# STM32.net
KiCad netlist of a schematic drawn in Altium Designer
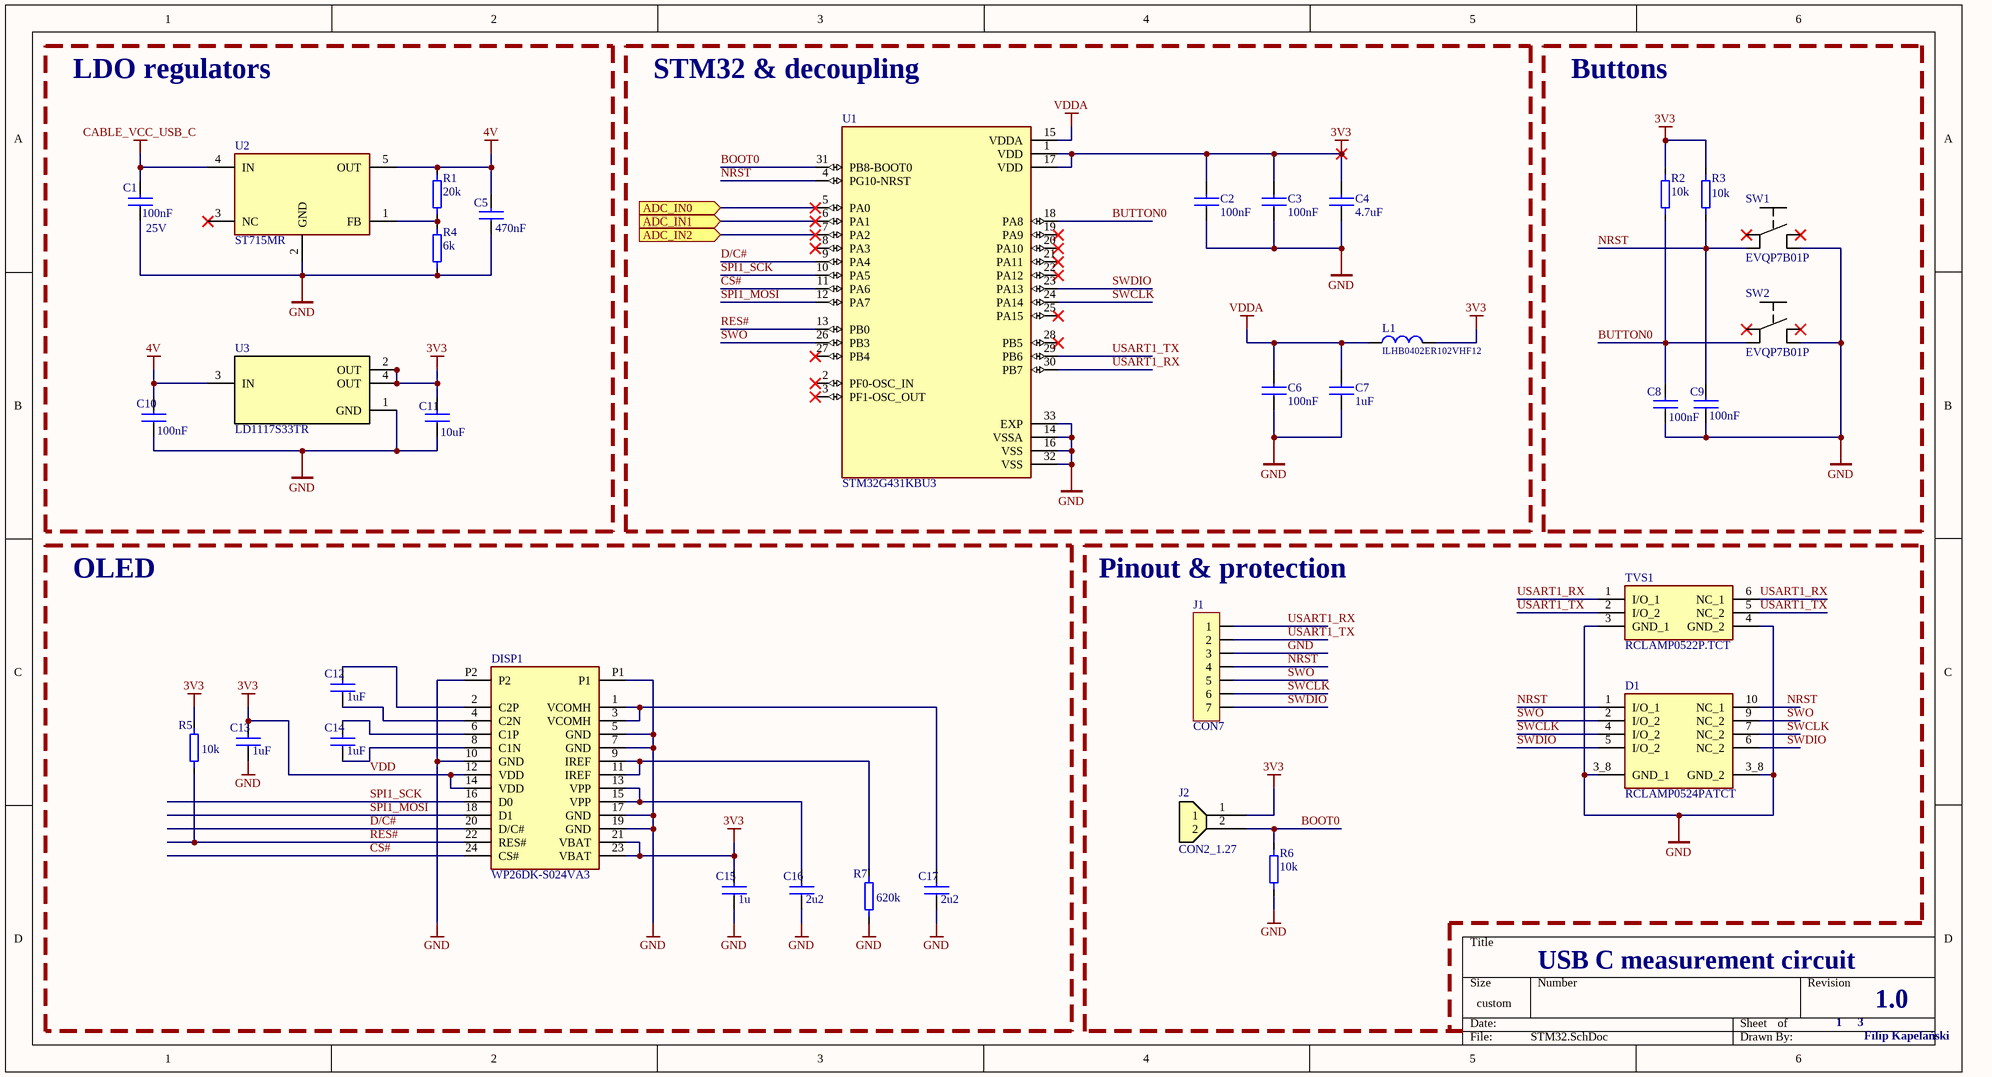
[diagram p0: STM32.SchDoc]

(export (version "E")
  (design (tool "Eeschema 10.0.6"))
  (components
    (comp (ref "C1")
      (value "100nF")
      (footprint "C0402")
      (description "Kondensator ceramiczny SMD")
      (fields (field (name "VOLTAGE") "25V"))
      (libsource (lib "n16_discrete") (part "C"))
    )
    (comp (ref "C2")
      (value "100nF")
      (footprint "C0402")
      (description "Kondensator ceramiczny SMD")
      (libsource (lib "n16_discrete") (part "C"))
    )
    (comp (ref "C3")
      (value "100nF")
      (footprint "C0402")
      (description "Kondensator ceramiczny SMD")
      (libsource (lib "n16_discrete") (part "C"))
    )
    (comp (ref "C4")
      (value "4.7uF")
      (footprint "C0402")
      (description "Kondensator ceramiczny SMD")
      (libsource (lib "n16_discrete") (part "C"))
    )
    (comp (ref "C5")
      (value "470nF")
      (footprint "C0402")
      (description "Kondensator ceramiczny SMD")
      (libsource (lib "n16_discrete") (part "C"))
    )
    (comp (ref "C6")
      (value "100nF")
      (footprint "C0402")
      (description "Kondensator ceramiczny SMD")
      (libsource (lib "n16_discrete") (part "C"))
    )
    (comp (ref "C7")
      (value "1uF")
      (footprint "C0402")
      (description "Kondensator ceramiczny SMD")
      (libsource (lib "n16_discrete") (part "C"))
    )
    (comp (ref "C8")
      (value "100nF")
      (footprint "C0402")
      (description "Kondensator ceramiczny SMD")
      (libsource (lib "n16_discrete") (part "C"))
    )
    (comp (ref "C9")
      (value "100nF")
      (footprint "C0402")
      (description "Kondensator ceramiczny SMD")
      (libsource (lib "n16_discrete") (part "C"))
    )
    (comp (ref "C10")
      (value "100nF")
      (footprint "C0402")
      (description "Kondensator ceramiczny SMD")
      (libsource (lib "n16_discrete") (part "C"))
    )
    (comp (ref "C11")
      (value "10uF")
      (footprint "C0402")
      (description "Kondensator ceramiczny SMD")
      (libsource (lib "n16_discrete") (part "C"))
    )
    (comp (ref "C12")
      (value "1uF")
      (footprint "C0402")
      (description "Kondensator ceramiczny SMD")
      (libsource (lib "n16_discrete") (part "C"))
    )
    (comp (ref "C13")
      (value "1uF")
      (footprint "C0402")
      (description "Kondensator ceramiczny SMD")
      (libsource (lib "n16_discrete") (part "C"))
    )
    (comp (ref "C14")
      (value "1uF")
      (footprint "C0402")
      (description "Kondensator ceramiczny SMD")
      (libsource (lib "n16_discrete") (part "C"))
    )
    (comp (ref "C15")
      (value "1u")
      (footprint "C0603")
      (description "Kondensator ceramiczny SMD")
      (libsource (lib "n16_discrete") (part "C"))
    )
    (comp (ref "C16")
      (value "2u2")
      (footprint "C0402")
      (description "Kondensator ceramiczny SMD")
      (libsource (lib "n16_discrete") (part "C"))
    )
    (comp (ref "C17")
      (value "2u2")
      (footprint "C0402")
      (description "Kondensator ceramiczny SMD")
      (libsource (lib "n16_discrete") (part "C"))
    )
    (comp (ref "D1")
      (value "RCLAMP0524PATCT")
      (footprint "DIO_RCLAMP0524PATCT")
      (description "15V Clamp 5A (8/20Âµs) Ipp Tvs Diode Surface Mount SLP2510P8")
      (fields (field (name "MF") "Semtech Corporation"))
      (libsource (lib "MyLibs") (part "RCLAMP0524PATCT"))
    )
    (comp (ref "DISP1")
      (value "WP26DK-S024VA3")
      (footprint "WP26DK-S024VA3")
      (libsource (lib "Optoelectronics") (part "WP26DK-S024VA3"))
    )
    (comp (ref "J1")
      (value "CON7")
      (footprint "SIP7")
      (description "Connector")
      (libsource (lib "n16_connector") (part "CON7"))
    )
    (comp (ref "J2")
      (value "CON2_1.27")
      (footprint "CON2_1.27")
      (description "Złącze: kołkowe; listwa kołkowa; męskie; PIN: 2; THT; proste; 1,27mm")
      (libsource (lib "n16_connector") (part "CON2_1.27"))
    )
    (comp (ref "L1")
      (value "ILHB0402ER102VHF12")
      (footprint "L0402")
      (description "Cewka/Koralik ferrytowy")
      (libsource (lib "n16_discrete") (part "L"))
    )
    (comp (ref "R1")
      (value "20k")
      (footprint "R0805")
      (description "Rezystor SMD")
      (libsource (lib "n16_discrete") (part "R"))
    )
    (comp (ref "R2")
      (value "10k")
      (footprint "R0402")
      (description "Rezystor SMD")
      (libsource (lib "n16_discrete") (part "R"))
    )
    (comp (ref "R3")
      (value "10k")
      (footprint "R0402")
      (description "Rezystor SMD")
      (libsource (lib "n16_discrete") (part "R"))
    )
    (comp (ref "R4")
      (value "6k")
      (footprint "R0805")
      (description "Rezystor SMD")
      (libsource (lib "n16_discrete") (part "R"))
    )
    (comp (ref "R5")
      (value "10k")
      (footprint "R0402")
      (description "Rezystor SMD")
      (libsource (lib "n16_discrete") (part "R"))
    )
    (comp (ref "R6")
      (value "10k")
      (footprint "R0402")
      (description "Rezystor SMD")
      (libsource (lib "uEproject23") (part "R"))
    )
    (comp (ref "R7")
      (value "620k")
      (footprint "R0402")
      (description "Rezystor SMD")
      (libsource (lib "n16_discrete") (part "R"))
    )
    (comp (ref "SW1")
      (value "EVQP7B01P")
      (footprint "EVQP7B01P")
      (description "Switch Tactile N.O. SPST Rectangular Button J-Bend 0.05A 12VDC 2.2N SMD T/R")
      (libsource (lib "Switche") (part "EVQP7B01P"))
    )
    (comp (ref "SW2")
      (value "EVQP7B01P")
      (footprint "EVQP7B01P")
      (description "Switch Tactile N.O. SPST Rectangular Button J-Bend 0.05A 12VDC 2.2N SMD T/R")
      (libsource (lib "Switche") (part "EVQP7B01P"))
    )
    (comp (ref "TVS1")
      (value "RCLAMP0522P.TCT")
      (footprint "RCLAMP0522PTCT")
      (description "TVS Diode (Bi-directional)")
      (fields (field (name "MOUSER PART NUMBER") "947-RCLAMP0522P.TCT"))
      (libsource (lib "MyLibs") (part "RCLAMP0522P.TCT"))
    )
    (comp (ref "U1")
      (value "STM32G431KBU3")
      (footprint "STM32G431KBU3")
      (libsource (lib "STM32") (part "STM32G431KBU3"))
    )
    (comp (ref "U2")
      (value "ST715MR")
      (footprint "ST715MR")
      (description "Linear Voltage Regulator IC Positive Adjustable 1 Output 85mA SOT-23-5")
      (libsource (lib "LDO") (part "ST715MR"))
    )
    (comp (ref "U3")
      (value "LD1117S33TR")
      (footprint "LD1117S33TR")
      (description "Linear Voltage Regulator IC Positive Fixed 1 Output 800mA SOT-223")
      (libsource (lib "LDO") (part "LD1117S33TR"))
    )
  )
  (nets
    (net (code "1") (name "/ADC_IN0") (class "Default")
      (node (ref "U1") (pin "5") (pinfunction "PA0_5") (pintype "bidirectional+no_connect"))
    )
    (net (code "2") (name "/ADC_IN1") (class "Default")
      (node (ref "U1") (pin "6") (pinfunction "PA1_6") (pintype "bidirectional+no_connect"))
    )
    (net (code "3") (name "/ADC_IN2") (class "Default")
      (node (ref "U1") (pin "7") (pinfunction "PA2_7") (pintype "bidirectional+no_connect"))
    )
    (net (code "4") (name "/BOOT0") (class "Default")
      (node (ref "J2") (pin "2") (pinfunction "2_2") (pintype "passive"))
      (node (ref "R6") (pin "2") (pinfunction "2_2") (pintype "passive"))
      (node (ref "U1") (pin "31") (pinfunction "PB8-BOOT0_31") (pintype "bidirectional"))
    )
    (net (code "5") (name "/BUTTON0") (class "Default")
      (node (ref "C8") (pin "2") (pinfunction "2_2") (pintype "passive"))
      (node (ref "R2") (pin "2") (pinfunction "2_2") (pintype "passive"))
      (node (ref "SW2") (pin "1") (pinfunction "P_1") (pintype "passive"))
      (node (ref "U1") (pin "18") (pinfunction "PA8_18") (pintype "bidirectional"))
    )
    (net (code "6") (name "/CS#") (class "Default")
      (node (ref "DISP1") (pin "24") (pinfunction "CS#_24") (pintype "passive"))
      (node (ref "U1") (pin "11") (pinfunction "PA6_11") (pintype "bidirectional"))
    )
    (net (code "7") (name "/D{slash}C#") (class "Default")
      (node (ref "DISP1") (pin "20") (pinfunction "D/C#_20") (pintype "passive"))
      (node (ref "U1") (pin "9") (pinfunction "PA4_9") (pintype "bidirectional"))
    )
    (net (code "8") (name "/NRST") (class "Default")
      (node (ref "C9") (pin "2") (pinfunction "2_2") (pintype "passive"))
      (node (ref "D1") (pin "1") (pinfunction "I/O_1_1") (pintype "passive"))
      (node (ref "D1") (pin "10") (pinfunction "NC_1_10") (pintype "passive"))
      (node (ref "J1") (pin "4") (pinfunction "4_4") (pintype "passive"))
      (node (ref "R3") (pin "2") (pinfunction "2_2") (pintype "passive"))
      (node (ref "SW1") (pin "1") (pinfunction "P_1") (pintype "passive"))
      (node (ref "U1") (pin "4") (pinfunction "PG10-NRST_4") (pintype "bidirectional"))
    )
    (net (code "9") (name "/RES#") (class "Default")
      (node (ref "DISP1") (pin "22") (pinfunction "RES#_22") (pintype "passive"))
      (node (ref "R5") (pin "2") (pinfunction "2_2") (pintype "passive"))
      (node (ref "U1") (pin "13") (pinfunction "PB0_13") (pintype "bidirectional"))
    )
    (net (code "10") (name "/SPI1_MOSI") (class "Default")
      (node (ref "DISP1") (pin "18") (pinfunction "D1_18") (pintype "passive"))
      (node (ref "U1") (pin "12") (pinfunction "PA7_12") (pintype "bidirectional"))
    )
    (net (code "11") (name "/SPI1_SCK") (class "Default")
      (node (ref "DISP1") (pin "16") (pinfunction "D0_16") (pintype "passive"))
      (node (ref "U1") (pin "10") (pinfunction "PA5_10") (pintype "bidirectional"))
    )
    (net (code "12") (name "/SWCLK") (class "Default")
      (node (ref "D1") (pin "4") (pinfunction "I/O_2_4") (pintype "passive"))
      (node (ref "D1") (pin "7") (pinfunction "NC_2_7") (pintype "passive"))
      (node (ref "J1") (pin "6") (pinfunction "6_6") (pintype "passive"))
      (node (ref "U1") (pin "24") (pinfunction "PA14_24") (pintype "bidirectional"))
    )
    (net (code "13") (name "/SWDIO") (class "Default")
      (node (ref "D1") (pin "5") (pinfunction "I/O_2_5") (pintype "passive"))
      (node (ref "D1") (pin "6") (pinfunction "NC_2_6") (pintype "passive"))
      (node (ref "J1") (pin "7") (pinfunction "7_7") (pintype "passive"))
      (node (ref "U1") (pin "23") (pinfunction "PA13_23") (pintype "bidirectional"))
    )
    (net (code "14") (name "/SWO") (class "Default")
      (node (ref "D1") (pin "2") (pinfunction "I/O_2_2") (pintype "passive"))
      (node (ref "D1") (pin "9") (pinfunction "NC_2_9") (pintype "passive"))
      (node (ref "J1") (pin "5") (pinfunction "5_5") (pintype "passive"))
      (node (ref "U1") (pin "26") (pinfunction "PB3_26") (pintype "bidirectional"))
    )
    (net (code "15") (name "/USART1_RX") (class "Default")
      (node (ref "J1") (pin "1") (pinfunction "1_1") (pintype "passive"))
      (node (ref "TVS1") (pin "1") (pinfunction "I/O_1_1") (pintype "passive"))
      (node (ref "TVS1") (pin "6") (pinfunction "NC_1_6") (pintype "passive"))
      (node (ref "U1") (pin "30") (pinfunction "PB7_30") (pintype "bidirectional"))
    )
    (net (code "16") (name "/USART1_TX") (class "Default")
      (node (ref "J1") (pin "2") (pinfunction "2_2") (pintype "passive"))
      (node (ref "TVS1") (pin "2") (pinfunction "I/O_2_2") (pintype "passive"))
      (node (ref "TVS1") (pin "5") (pinfunction "NC_2_5") (pintype "passive"))
      (node (ref "U1") (pin "29") (pinfunction "PB6_29") (pintype "bidirectional"))
    )
    (net (code "17") (name "3V3") (class "Default")
      (node (ref "C11") (pin "2") (pinfunction "2_2") (pintype "passive"))
      (node (ref "C13") (pin "2") (pinfunction "2_2") (pintype "passive"))
      (node (ref "C15") (pin "2") (pinfunction "2_2") (pintype "passive"))
      (node (ref "C2") (pin "2") (pinfunction "2_2") (pintype "passive"))
      (node (ref "C3") (pin "2") (pinfunction "2_2") (pintype "passive"))
      (node (ref "C4") (pin "2") (pinfunction "2_2") (pintype "passive"))
      (node (ref "DISP1") (pin "12") (pinfunction "VDD_12") (pintype "passive"))
      (node (ref "DISP1") (pin "14") (pinfunction "VDD_14") (pintype "passive"))
      (node (ref "DISP1") (pin "21") (pinfunction "VBAT_21") (pintype "passive"))
      (node (ref "DISP1") (pin "23") (pinfunction "VBAT_23") (pintype "passive"))
      (node (ref "J2") (pin "1") (pinfunction "1_1") (pintype "passive"))
      (node (ref "L1") (pin "1") (pinfunction "1_1") (pintype "passive"))
      (node (ref "R2") (pin "1") (pinfunction "1_1") (pintype "passive"))
      (node (ref "R3") (pin "1") (pinfunction "1_1") (pintype "passive"))
      (node (ref "R5") (pin "1") (pinfunction "1_1") (pintype "passive"))
      (node (ref "U1") (pin "1") (pinfunction "VDD_1") (pintype "power_in"))
      (node (ref "U1") (pin "17") (pinfunction "VDD_17") (pintype "power_in"))
      (node (ref "U3") (pin "2") (pinfunction "OUT_2") (pintype "power_in"))
      (node (ref "U3") (pin "4") (pinfunction "OUT_4") (pintype "power_in"))
    )
    (net (code "18") (name "4V") (class "Default")
      (node (ref "C10") (pin "2") (pinfunction "2_2") (pintype "passive"))
      (node (ref "C5") (pin "2") (pinfunction "2_2") (pintype "passive"))
      (node (ref "R1") (pin "1") (pinfunction "1_1") (pintype "passive"))
      (node (ref "U2") (pin "5") (pinfunction "OUT_5") (pintype "power_in"))
      (node (ref "U3") (pin "3") (pinfunction "IN_3") (pintype "power_in"))
    )
    (net (code "19") (name "CABLE_VCC_USB_C") (class "Default")
      (node (ref "C1") (pin "2") (pinfunction "2_2") (pintype "passive"))
      (node (ref "U2") (pin "4") (pinfunction "IN_4") (pintype "passive"))
    )
    (net (code "20") (name "GND") (class "Default")
      (node (ref "C1") (pin "1") (pinfunction "1_1") (pintype "passive"))
      (node (ref "C10") (pin "1") (pinfunction "1_1") (pintype "passive"))
      (node (ref "C11") (pin "1") (pinfunction "1_1") (pintype "passive"))
      (node (ref "C13") (pin "1") (pinfunction "1_1") (pintype "passive"))
      (node (ref "C15") (pin "1") (pinfunction "1_1") (pintype "passive"))
      (node (ref "C16") (pin "1") (pinfunction "1_1") (pintype "passive"))
      (node (ref "C17") (pin "1") (pinfunction "1_1") (pintype "passive"))
      (node (ref "C2") (pin "1") (pinfunction "1_1") (pintype "passive"))
      (node (ref "C3") (pin "1") (pinfunction "1_1") (pintype "passive"))
      (node (ref "C4") (pin "1") (pinfunction "1_1") (pintype "passive"))
      (node (ref "C5") (pin "1") (pinfunction "1_1") (pintype "passive"))
      (node (ref "C6") (pin "1") (pinfunction "1_1") (pintype "passive"))
      (node (ref "C7") (pin "1") (pinfunction "1_1") (pintype "passive"))
      (node (ref "C8") (pin "1") (pinfunction "1_1") (pintype "passive"))
      (node (ref "C9") (pin "1") (pinfunction "1_1") (pintype "passive"))
      (node (ref "D1") (pin "3_8") (pinfunction "GND_1_3_8") (pintype "passive"))
      (node (ref "DISP1") (pin "10") (pinfunction "GND_10") (pintype "passive"))
      (node (ref "DISP1") (pin "17") (pinfunction "GND_17") (pintype "passive"))
      (node (ref "DISP1") (pin "19") (pinfunction "GND_19") (pintype "passive"))
      (node (ref "DISP1") (pin "5") (pinfunction "GND_5") (pintype "passive"))
      (node (ref "DISP1") (pin "7") (pinfunction "GND_7") (pintype "passive"))
      (node (ref "DISP1") (pin "P1") (pinfunction "P1_P1") (pintype "power_in"))
      (node (ref "DISP1") (pin "P2") (pinfunction "P2_P2") (pintype "power_in"))
      (node (ref "J1") (pin "3") (pinfunction "3_3") (pintype "passive"))
      (node (ref "R4") (pin "2") (pinfunction "2_2") (pintype "passive"))
      (node (ref "R6") (pin "1") (pinfunction "1_1") (pintype "passive"))
      (node (ref "R7") (pin "2") (pinfunction "2_2") (pintype "passive"))
      (node (ref "SW1") (pin "2") (pinfunction "S_2") (pintype "passive"))
      (node (ref "SW2") (pin "2") (pinfunction "S_2") (pintype "passive"))
      (node (ref "TVS1") (pin "3") (pinfunction "GND_1_3") (pintype "passive"))
      (node (ref "TVS1") (pin "4") (pinfunction "GND_2_4") (pintype "passive"))
      (node (ref "U1") (pin "14") (pinfunction "VSSA_14") (pintype "power_in"))
      (node (ref "U1") (pin "16") (pinfunction "VSS_16") (pintype "power_in"))
      (node (ref "U1") (pin "32") (pinfunction "VSS_32") (pintype "power_in"))
      (node (ref "U1") (pin "33") (pinfunction "EXP_33") (pintype "power_in"))
      (node (ref "U2") (pin "2") (pinfunction "GND_2") (pintype "passive"))
      (node (ref "U3") (pin "1") (pinfunction "GND_1") (pintype "power_in"))
    )
    (net (code "21") (name "Net-(C16-Pad2)") (class "Default")
      (node (ref "C16") (pin "2") (pinfunction "2_2") (pintype "passive"))
      (node (ref "DISP1") (pin "13") (pinfunction "VPP_13") (pintype "passive"))
      (node (ref "DISP1") (pin "15") (pinfunction "VPP_15") (pintype "passive"))
    )
    (net (code "22") (name "Net-(C17-Pad2)") (class "Default")
      (node (ref "C17") (pin "2") (pinfunction "2_2") (pintype "passive"))
      (node (ref "DISP1") (pin "1") (pinfunction "VCOMH_1") (pintype "passive"))
      (node (ref "DISP1") (pin "3") (pinfunction "VCOMH_3") (pintype "passive"))
    )
    (net (code "23") (name "Net-(DISP1-C1N)") (class "Default")
      (node (ref "C14") (pin "1") (pinfunction "1_1") (pintype "passive"))
      (node (ref "DISP1") (pin "8") (pinfunction "C1N_8") (pintype "passive"))
    )
    (net (code "24") (name "Net-(DISP1-C1P)") (class "Default")
      (node (ref "C14") (pin "2") (pinfunction "2_2") (pintype "passive"))
      (node (ref "DISP1") (pin "6") (pinfunction "C1P_6") (pintype "passive"))
    )
    (net (code "25") (name "Net-(DISP1-C2N)") (class "Default")
      (node (ref "C12") (pin "1") (pinfunction "1_1") (pintype "passive"))
      (node (ref "DISP1") (pin "4") (pinfunction "C2N_4") (pintype "passive"))
    )
    (net (code "26") (name "Net-(DISP1-C2P)") (class "Default")
      (node (ref "C12") (pin "2") (pinfunction "2_2") (pintype "passive"))
      (node (ref "DISP1") (pin "2") (pinfunction "C2P_2") (pintype "passive"))
    )
    (net (code "27") (name "Net-(DISP1-IREF-Pad11)") (class "Default")
      (node (ref "DISP1") (pin "11") (pinfunction "IREF_11") (pintype "passive"))
      (node (ref "DISP1") (pin "9") (pinfunction "IREF_9") (pintype "passive"))
      (node (ref "R7") (pin "1") (pinfunction "1_1") (pintype "passive"))
    )
    (net (code "28") (name "Net-(U2-FB)") (class "Default")
      (node (ref "R1") (pin "2") (pinfunction "2_2") (pintype "passive"))
      (node (ref "R4") (pin "1") (pinfunction "1_1") (pintype "passive"))
      (node (ref "U2") (pin "1") (pinfunction "FB_1") (pintype "power_in"))
    )
    (net (code "29") (name "VDDA") (class "Default")
      (node (ref "C6") (pin "2") (pinfunction "2_2") (pintype "passive"))
      (node (ref "C7") (pin "2") (pinfunction "2_2") (pintype "passive"))
      (node (ref "L1") (pin "2") (pinfunction "2_2") (pintype "passive"))
      (node (ref "U1") (pin "15") (pinfunction "VDDA_15") (pintype "power_in"))
    )
    (net (code "30") (name "unconnected-(SW1-P1-Pad1')") (class "Default")
      (node (ref "SW1") (pin "1'") (pinfunction "P1_1'") (pintype "passive+no_connect"))
    )
    (net (code "31") (name "unconnected-(SW1-S1-Pad2')") (class "Default")
      (node (ref "SW1") (pin "2'") (pinfunction "S1_2'") (pintype "passive+no_connect"))
    )
    (net (code "32") (name "unconnected-(SW2-P1-Pad1')") (class "Default")
      (node (ref "SW2") (pin "1'") (pinfunction "P1_1'") (pintype "passive+no_connect"))
    )
    (net (code "33") (name "unconnected-(SW2-S1-Pad2')") (class "Default")
      (node (ref "SW2") (pin "2'") (pinfunction "S1_2'") (pintype "passive+no_connect"))
    )
    (net (code "34") (name "unconnected-(U1-PA3-Pad8)") (class "Default")
      (node (ref "U1") (pin "8") (pinfunction "PA3_8") (pintype "bidirectional+no_connect"))
    )
    (net (code "35") (name "unconnected-(U1-PA9-Pad19)") (class "Default")
      (node (ref "U1") (pin "19") (pinfunction "PA9_19") (pintype "bidirectional+no_connect"))
    )
    (net (code "36") (name "unconnected-(U1-PA10-Pad20)") (class "Default")
      (node (ref "U1") (pin "20") (pinfunction "PA10_20") (pintype "bidirectional+no_connect"))
    )
    (net (code "37") (name "unconnected-(U1-PA11-Pad21)") (class "Default")
      (node (ref "U1") (pin "21") (pinfunction "PA11_21") (pintype "bidirectional+no_connect"))
    )
    (net (code "38") (name "unconnected-(U1-PA12-Pad22)") (class "Default")
      (node (ref "U1") (pin "22") (pinfunction "PA12_22") (pintype "bidirectional+no_connect"))
    )
    (net (code "39") (name "unconnected-(U1-PA15-Pad25)") (class "Default")
      (node (ref "U1") (pin "25") (pinfunction "PA15_25") (pintype "bidirectional+no_connect"))
    )
    (net (code "40") (name "unconnected-(U1-PB4-Pad27)") (class "Default")
      (node (ref "U1") (pin "27") (pinfunction "PB4_27") (pintype "bidirectional+no_connect"))
    )
    (net (code "41") (name "unconnected-(U1-PB5-Pad28)") (class "Default")
      (node (ref "U1") (pin "28") (pinfunction "PB5_28") (pintype "bidirectional+no_connect"))
    )
    (net (code "42") (name "unconnected-(U1-PF0-OSC_IN-Pad2)") (class "Default")
      (node (ref "U1") (pin "2") (pinfunction "PF0-OSC_IN_2") (pintype "bidirectional+no_connect"))
    )
    (net (code "43") (name "unconnected-(U1-PF1-OSC_OUT-Pad3)") (class "Default")
      (node (ref "U1") (pin "3") (pinfunction "PF1-OSC_OUT_3") (pintype "bidirectional+no_connect"))
    )
    (net (code "44") (name "unconnected-(U2-NC-Pad3)") (class "Default")
      (node (ref "U2") (pin "3") (pinfunction "NC_3") (pintype "passive+no_connect"))
    )
  )
)
